# delayStarter.net
KiCad netlist of a schematic drawn in EAGLE
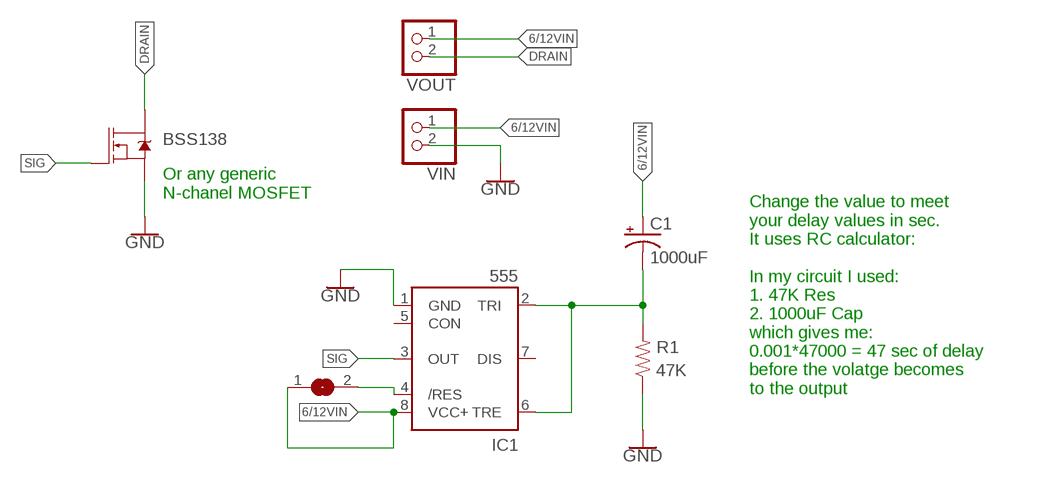
[diagram p0: schematic, sheet 1]

(export (version "E")
  (design (tool "Eeschema 10.0.6"))
  (components
    (comp (ref "BSS138")
      (value "BSS138")
      (footprint "eagle-import:SOT23-3")
      (libsource (lib "eagle-import") (part "MOSFET-NCH-AO3404A"))
    )
    (comp (ref "C1")
      (value "1000uF")
      (footprint "eagle-import:153CLV-0810")
      (libsource (lib "eagle-import") (part "CPOL-US153CLV-0810"))
    )
    (comp (ref "IC1")
      (value "555")
      (footprint "eagle-import:SO08")
      (libsource (lib "eagle-import") (part "555D"))
    )
    (comp (ref "R1")
      (value "47K")
      (footprint "eagle-import:0603")
      (libsource (lib "eagle-import") (part "470OHM-0603-1/10W-1%"))
    )
    (comp (ref "SJ1")
      (value "JUMPER_SJ")
      (footprint "eagle-import:JUMPER_SJ")
      (libsource (lib "eagle-import") (part "JUMPER_SJ"))
    )
    (comp (ref "VIN")
      (value "ONBOARDCONTROLINTERFACE_LED-BADGE_SCHEMATIC_ADAFRUIT_JST_2PIN-SMT-RA")
      (footprint "eagle-import:ONBOARDCONTROLINTERFACE_LED-BADGE_SCHEMATIC_ADAFRUIT_JST-PH-2-SMT-RA")
      (libsource (lib "eagle-import") (part "ONBOARDCONTROLINTERFACE_LED-BADGE_SCHEMATIC_ADAFRUIT_JST_2PIN-SMT-RA"))
    )
    (comp (ref "VOUT")
      (value "ONBOARDCONTROLINTERFACE_LED-BADGE_SCHEMATIC_ADAFRUIT_JST_2PIN-SMT-RA")
      (footprint "eagle-import:ONBOARDCONTROLINTERFACE_LED-BADGE_SCHEMATIC_ADAFRUIT_JST-PH-2-SMT-RA")
      (libsource (lib "eagle-import") (part "ONBOARDCONTROLINTERFACE_LED-BADGE_SCHEMATIC_ADAFRUIT_JST_2PIN-SMT-RA"))
    )
  )
  (nets
    (net (code "1") (name "6{slash}12VIN") (class "Default")
      (node (ref "C1") (pin "+") (pinfunction "+_+") (pintype "passive"))
      (node (ref "IC1") (pin "8") (pinfunction "VCC+_8") (pintype "power_in"))
      (node (ref "SJ1") (pin "1") (pinfunction "1_1") (pintype "passive"))
      (node (ref "VIN") (pin "1") (pinfunction "2_1") (pintype "passive"))
      (node (ref "VOUT") (pin "1") (pinfunction "2_1") (pintype "passive"))
    )
    (net (code "2") (name "DRAIN") (class "Default")
      (node (ref "BSS138") (pin "3") (pinfunction "D_3") (pintype "bidirectional"))
      (node (ref "VOUT") (pin "2") (pinfunction "1_2") (pintype "passive"))
    )
    (net (code "3") (name "GND") (class "Default")
      (node (ref "BSS138") (pin "2") (pinfunction "S_2") (pintype "bidirectional"))
      (node (ref "IC1") (pin "1") (pinfunction "GND_1") (pintype "power_in"))
      (node (ref "R1") (pin "1") (pinfunction "1_1") (pintype "passive"))
      (node (ref "VIN") (pin "2") (pinfunction "1_2") (pintype "passive"))
    )
    (net (code "4") (name "Net-(IC1-TRE)") (class "Default")
      (node (ref "C1") (pin "-") (pinfunction "-_-") (pintype "passive"))
      (node (ref "IC1") (pin "2") (pinfunction "TRI_2") (pintype "input"))
      (node (ref "IC1") (pin "6") (pinfunction "TRE_6") (pintype "input"))
      (node (ref "R1") (pin "2") (pinfunction "2_2") (pintype "passive"))
    )
    (net (code "5") (name "Net-(IC1-{slash}RES)") (class "Default")
      (node (ref "IC1") (pin "4") (pinfunction "/RES_4") (pintype "input"))
      (node (ref "SJ1") (pin "2") (pinfunction "2_2") (pintype "passive"))
    )
    (net (code "6") (name "SIG") (class "Default")
      (node (ref "BSS138") (pin "1") (pinfunction "G_1") (pintype "bidirectional"))
      (node (ref "IC1") (pin "3") (pinfunction "OUT_3") (pintype "output"))
    )
    (net (code "7") (name "unconnected-(IC1-CON-Pad5)") (class "Default")
      (node (ref "IC1") (pin "5") (pinfunction "CON_5") (pintype "input"))
    )
    (net (code "8") (name "unconnected-(IC1-DIS-Pad7)") (class "Default")
      (node (ref "IC1") (pin "7") (pinfunction "DIS_7") (pintype "input"))
    )
  )
)
